# USBBridge.net
KiCad netlist of a schematic drawn in Altium Designer
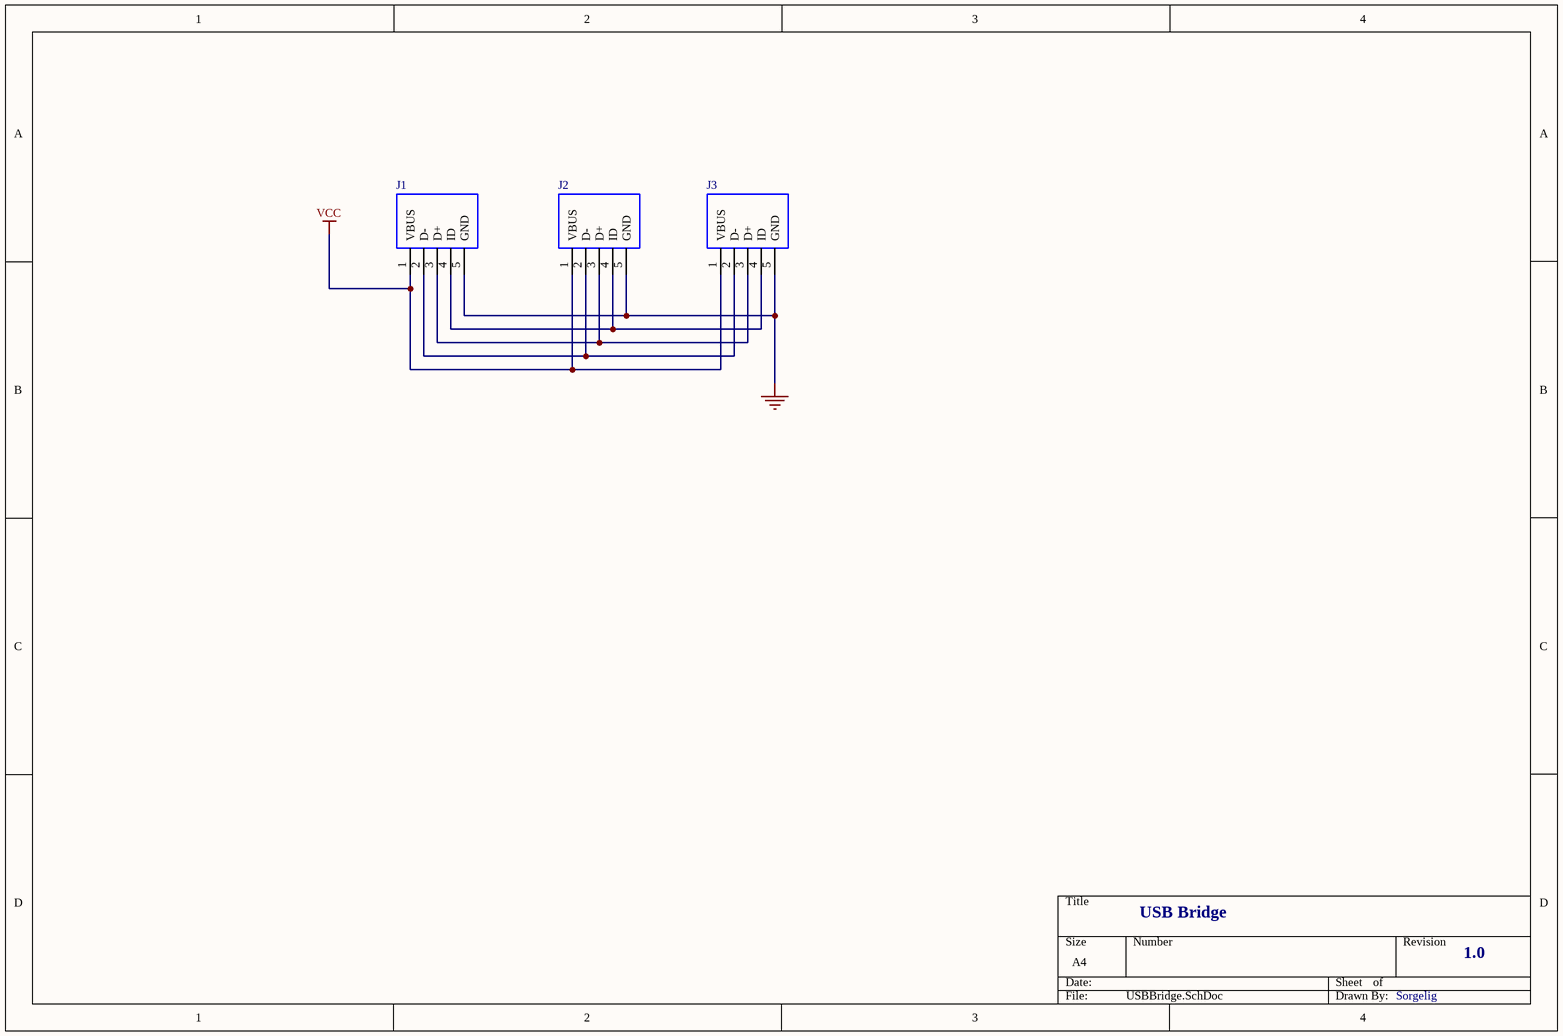
[diagram p0: USBBridge.SchDoc]

(export (version "E")
  (design (tool "Eeschema 10.0.6"))
  (components
    (comp (ref "J1")
      (value "MicroUSB THT")
      (footprint "MicroUSB THT")
      (fields
        (field (name "MANUFACTURER_PART_NUMBER") "47346-0001")
        (field (name "MOUSER PART NUMBER") "538-47346-0001")
        (field (name "RS PART NUMBER") "7025475P")
      )
      (libsource (lib "lib") (part "MicroUSB THT"))
    )
    (comp (ref "J2")
      (value "MicroUSB THT")
      (footprint "MicroUSB THT")
      (fields
        (field (name "MANUFACTURER_PART_NUMBER") "47346-0001")
        (field (name "MOUSER PART NUMBER") "538-47346-0001")
        (field (name "RS PART NUMBER") "7025475P")
      )
      (libsource (lib "lib") (part "MicroUSB THT"))
    )
    (comp (ref "J3")
      (value "MicroUSB THT")
      (footprint "MicroUSB THT")
      (fields
        (field (name "MANUFACTURER_PART_NUMBER") "47346-0001")
        (field (name "MOUSER PART NUMBER") "538-47346-0001")
        (field (name "RS PART NUMBER") "7025475P")
      )
      (libsource (lib "lib") (part "MicroUSB THT"))
    )
  )
  (nets
    (net (code "1") (name "GND") (class "Default")
      (node (ref "J1") (pin "5") (pinfunction "GND_5") (pintype "passive"))
      (node (ref "J2") (pin "5") (pinfunction "GND_5") (pintype "passive"))
      (node (ref "J3") (pin "5") (pinfunction "GND_5") (pintype "passive"))
    )
    (net (code "2") (name "Net-(J1-D+)") (class "Default")
      (node (ref "J1") (pin "3") (pinfunction "D+_3") (pintype "passive"))
      (node (ref "J2") (pin "3") (pinfunction "D+_3") (pintype "passive"))
      (node (ref "J3") (pin "3") (pinfunction "D+_3") (pintype "passive"))
    )
    (net (code "3") (name "Net-(J1-D-)") (class "Default")
      (node (ref "J1") (pin "2") (pinfunction "D-_2") (pintype "passive"))
      (node (ref "J2") (pin "2") (pinfunction "D-_2") (pintype "passive"))
      (node (ref "J3") (pin "2") (pinfunction "D-_2") (pintype "passive"))
    )
    (net (code "4") (name "Net-(J1-ID)") (class "Default")
      (node (ref "J1") (pin "4") (pinfunction "ID_4") (pintype "passive"))
      (node (ref "J2") (pin "4") (pinfunction "ID_4") (pintype "passive"))
      (node (ref "J3") (pin "4") (pinfunction "ID_4") (pintype "passive"))
    )
    (net (code "5") (name "VCC") (class "Default")
      (node (ref "J1") (pin "1") (pinfunction "VBUS_1") (pintype "passive"))
      (node (ref "J2") (pin "1") (pinfunction "VBUS_1") (pintype "passive"))
      (node (ref "J3") (pin "1") (pinfunction "VBUS_1") (pintype "passive"))
    )
  )
)
